# 140711_AriloTX_REV2_1_0.net
KiCad netlist of a schematic drawn in EAGLE
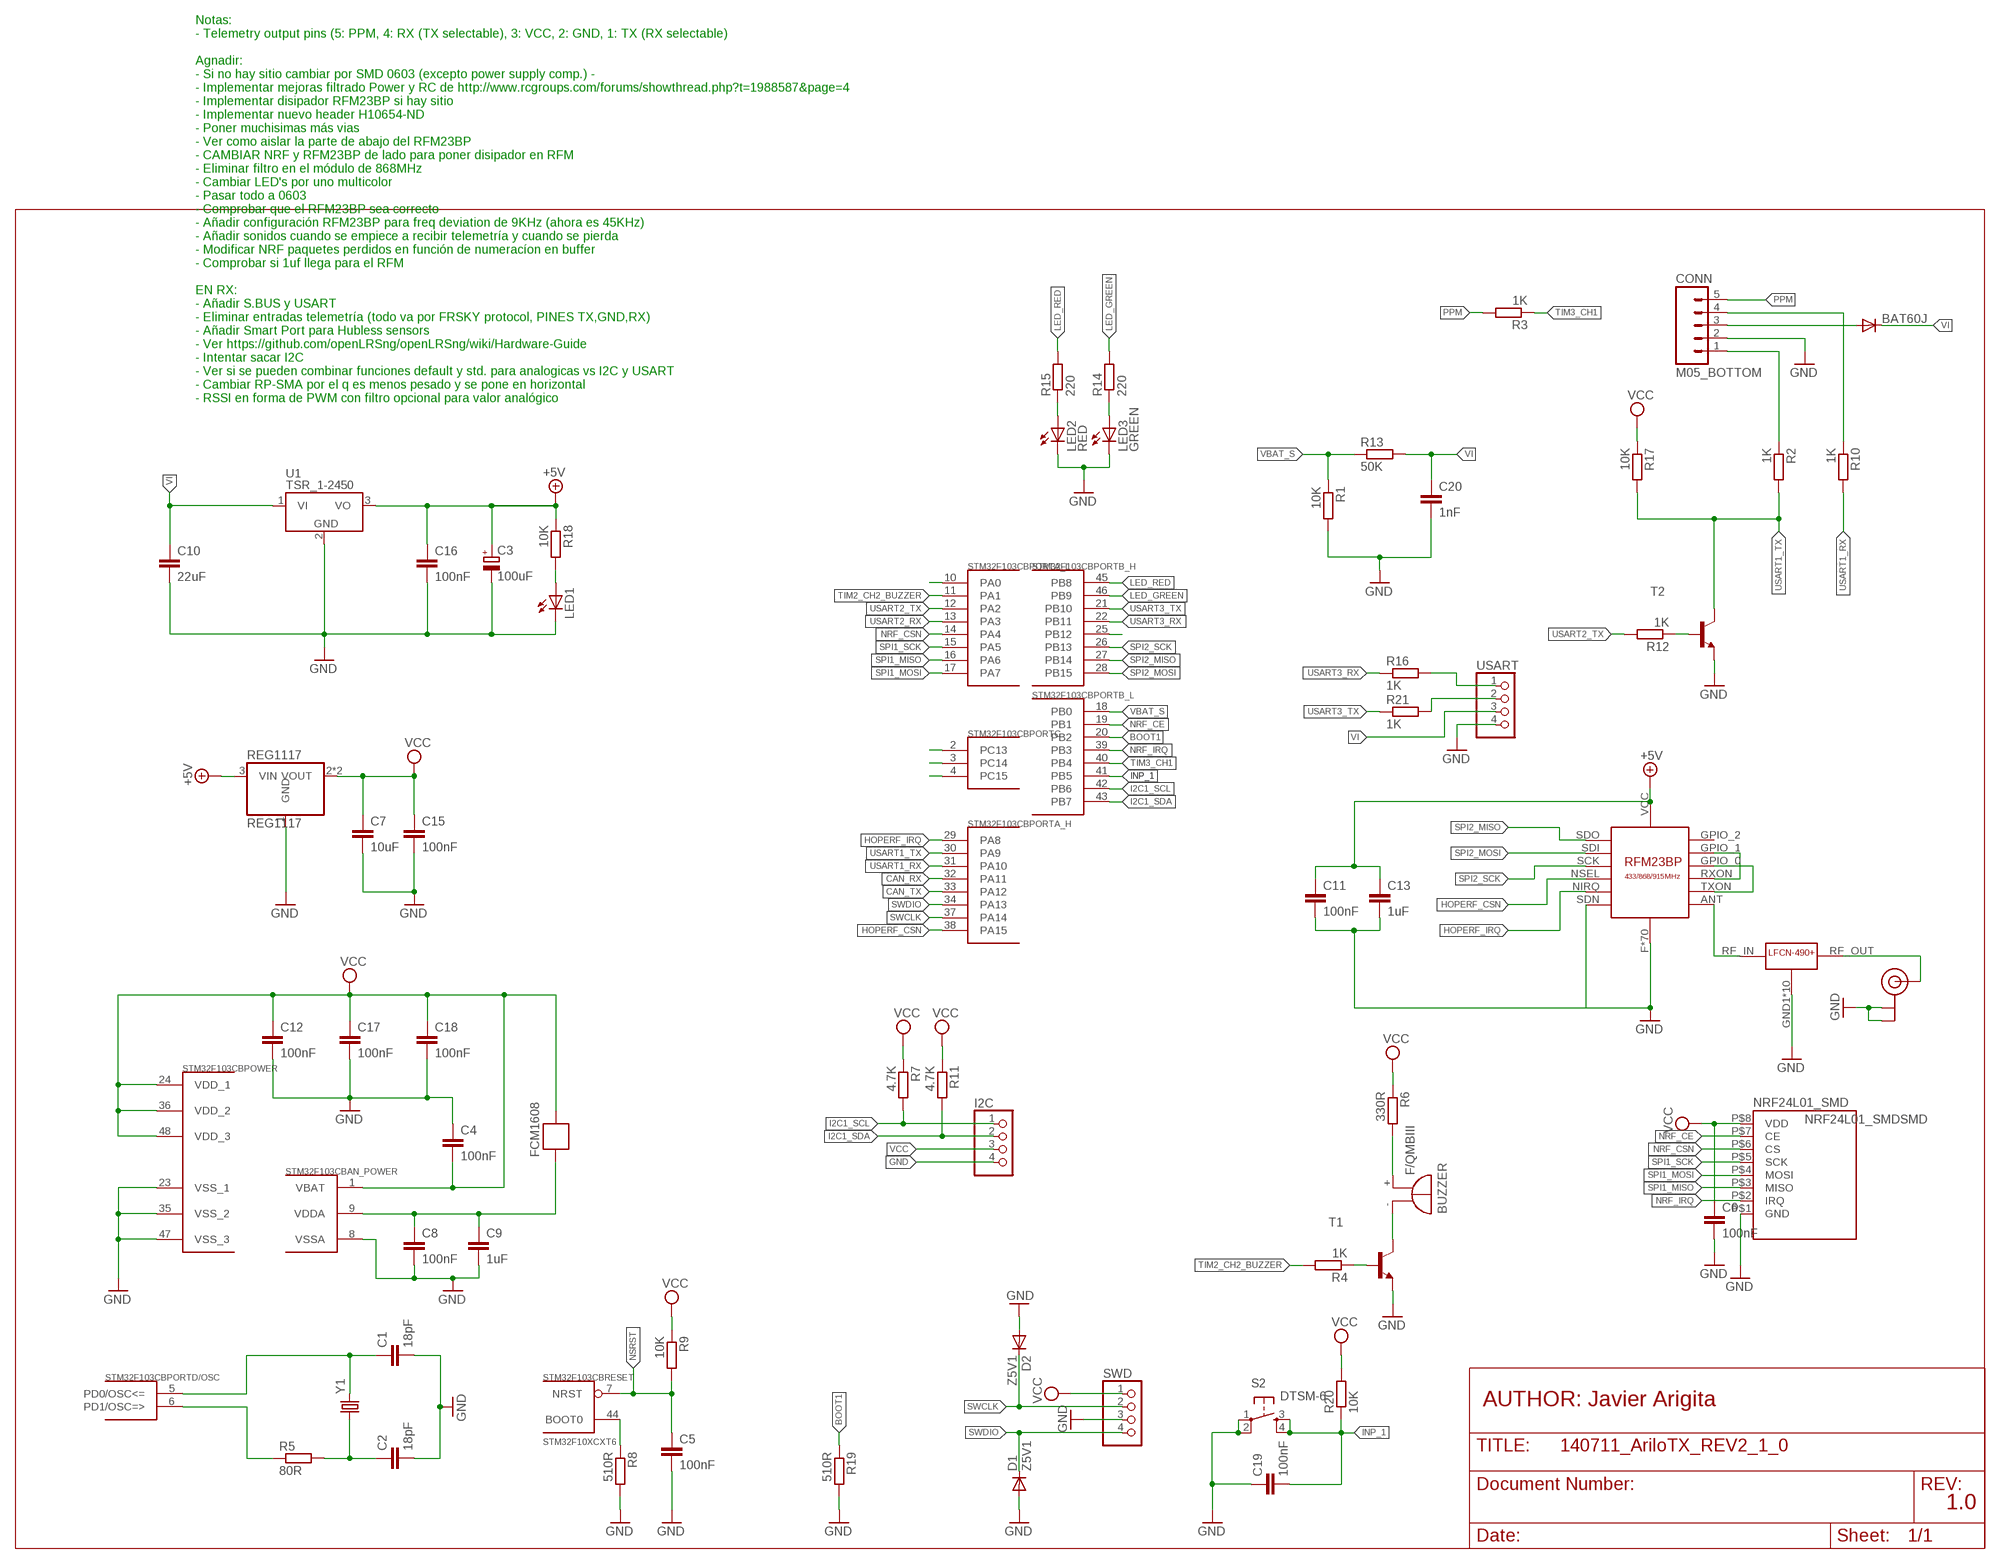
[diagram p0: schematic, sheet 1]

(export (version "E")
  (design (tool "Eeschema 10.0.6"))
  (components
    (comp (ref "BAT60J")
      (value "DIODE-SOD323-R")
      (footprint "eagle-import:SOD323-R")
      (libsource (lib "eagle-import") (part "DIODE-SOD323-R"))
    )
    (comp (ref "BUZZER")
      (value "F/QMBIII")
      (footprint "eagle-import:F_QMBIII")
      (libsource (lib "eagle-import") (part "F/QMBIII"))
    )
    (comp (ref "C1")
      (value "18pF")
      (footprint "eagle-import:C0603")
      (libsource (lib "eagle-import") (part "C-EUC0603"))
    )
    (comp (ref "C2")
      (value "18pF")
      (footprint "eagle-import:C0603")
      (libsource (lib "eagle-import") (part "C-EUC0603"))
    )
    (comp (ref "C3")
      (value "100uF")
      (footprint "eagle-import:SMC_B")
      (libsource (lib "eagle-import") (part "CPOL-EUSMCB"))
    )
    (comp (ref "C4")
      (value "100nF")
      (footprint "eagle-import:C0603")
      (libsource (lib "eagle-import") (part "C-EUC0603"))
    )
    (comp (ref "C5")
      (value "100nF")
      (footprint "eagle-import:C0603")
      (libsource (lib "eagle-import") (part "C-EUC0603"))
    )
    (comp (ref "C6")
      (value "100nF")
      (footprint "eagle-import:C0603")
      (libsource (lib "eagle-import") (part "C-EUC0603"))
    )
    (comp (ref "C7")
      (value "10uF")
      (footprint "eagle-import:C0805")
      (libsource (lib "eagle-import") (part "C-EUC0805"))
    )
    (comp (ref "C8")
      (value "100nF")
      (footprint "eagle-import:C0603")
      (libsource (lib "eagle-import") (part "C-EUC0603"))
    )
    (comp (ref "C9")
      (value "1uF")
      (footprint "eagle-import:C0603")
      (libsource (lib "eagle-import") (part "C-EUC0603"))
    )
    (comp (ref "C10")
      (value "22uF")
      (footprint "eagle-import:C3216")
      (libsource (lib "eagle-import") (part "resistor_C-EUC3216"))
    )
    (comp (ref "C11")
      (value "100nF")
      (footprint "eagle-import:C0603")
      (libsource (lib "eagle-import") (part "C-EUC0603"))
    )
    (comp (ref "C12")
      (value "100nF")
      (footprint "eagle-import:C0603")
      (libsource (lib "eagle-import") (part "C-EUC0603"))
    )
    (comp (ref "C13")
      (value "1uF")
      (footprint "eagle-import:C0603")
      (libsource (lib "eagle-import") (part "C-EUC0603"))
    )
    (comp (ref "C15")
      (value "100nF")
      (footprint "eagle-import:C0603")
      (libsource (lib "eagle-import") (part "C-EUC0603"))
    )
    (comp (ref "C16")
      (value "100nF")
      (footprint "eagle-import:C0603")
      (libsource (lib "eagle-import") (part "C-EUC0603"))
    )
    (comp (ref "C17")
      (value "100nF")
      (footprint "eagle-import:C0603")
      (libsource (lib "eagle-import") (part "C-EUC0603"))
    )
    (comp (ref "C18")
      (value "100nF")
      (footprint "eagle-import:C0603")
      (libsource (lib "eagle-import") (part "C-EUC0603"))
    )
    (comp (ref "C19")
      (value "100nF")
      (footprint "eagle-import:C0603")
      (libsource (lib "eagle-import") (part "C-EUC0603"))
    )
    (comp (ref "C20")
      (value "1nF")
      (footprint "eagle-import:C0603")
      (libsource (lib "eagle-import") (part "C-EUC0603"))
    )
    (comp (ref "CONN")
      (value "M05_BOTTOM")
      (footprint "eagle-import:M05_BOTTOM")
      (libsource (lib "eagle-import") (part "M05_BOTTOM"))
    )
    (comp (ref "D1")
      (value "Z5V1")
      (footprint "eagle-import:SOD323-R")
      (libsource (lib "eagle-import") (part "DIODE-SOD323-R"))
    )
    (comp (ref "D2")
      (value "Z5V1")
      (footprint "eagle-import:SOD323-R")
      (libsource (lib "eagle-import") (part "DIODE-SOD323-R"))
    )
    (comp (ref "FCM1608")
      (value "FERRITE-BEAD")
      (footprint "eagle-import:R0603")
      (libsource (lib "eagle-import") (part "FERRITE-BEAD"))
    )
    (comp (ref "I2C")
      (value "PINHD-1X4")
      (footprint "eagle-import:1X04")
      (libsource (lib "eagle-import") (part "PINHD-1X4"))
    )
    (comp (ref "LED1")
      (value "LEDCHIP-LED0603")
      (footprint "eagle-import:CHIP-LED0603")
      (libsource (lib "eagle-import") (part "LEDCHIP-LED0603"))
    )
    (comp (ref "LED2")
      (value "RED")
      (footprint "eagle-import:CHIP-LED0603")
      (libsource (lib "eagle-import") (part "LEDCHIP-LED0603"))
    )
    (comp (ref "LED3")
      (value "GREEN")
      (footprint "eagle-import:CHIP-LED0603")
      (libsource (lib "eagle-import") (part "LEDCHIP-LED0603"))
    )
    (comp (ref "NRF24L01_SMD")
      (value "NRF24L01_SMDSMD")
      (footprint "eagle-import:NRF24L01_SMD")
      (libsource (lib "eagle-import") (part "NRF24L01_SMDSMD"))
    )
    (comp (ref "R1")
      (value "10K")
      (footprint "eagle-import:R0603")
      (libsource (lib "eagle-import") (part "R-EU_R0603"))
    )
    (comp (ref "R2")
      (value "1K")
      (footprint "eagle-import:R0603")
      (libsource (lib "eagle-import") (part "R-EU_R0603"))
    )
    (comp (ref "R3")
      (value "1K")
      (footprint "eagle-import:R0603")
      (libsource (lib "eagle-import") (part "R-EU_R0603"))
    )
    (comp (ref "R4")
      (value "1K")
      (footprint "eagle-import:R0603")
      (libsource (lib "eagle-import") (part "R-EU_R0603"))
    )
    (comp (ref "R5")
      (value "80R")
      (footprint "eagle-import:R0603")
      (libsource (lib "eagle-import") (part "R-EU_R0603"))
    )
    (comp (ref "R6")
      (value "330R")
      (footprint "eagle-import:R0603")
      (libsource (lib "eagle-import") (part "R-EU_R0603"))
    )
    (comp (ref "R7")
      (value "4.7K")
      (footprint "eagle-import:R0603")
      (libsource (lib "eagle-import") (part "R-EU_R0603"))
    )
    (comp (ref "R8")
      (value "510R")
      (footprint "eagle-import:R0603")
      (libsource (lib "eagle-import") (part "R-EU_R0603"))
    )
    (comp (ref "R9")
      (value "10K")
      (footprint "eagle-import:R0603")
      (libsource (lib "eagle-import") (part "R-EU_R0603"))
    )
    (comp (ref "R10")
      (value "1K")
      (footprint "eagle-import:R0603")
      (libsource (lib "eagle-import") (part "R-EU_R0603"))
    )
    (comp (ref "R11")
      (value "4.7K")
      (footprint "eagle-import:R0603")
      (libsource (lib "eagle-import") (part "R-EU_R0603"))
    )
    (comp (ref "R12")
      (value "1K")
      (footprint "eagle-import:R0603")
      (libsource (lib "eagle-import") (part "R-EU_R0603"))
    )
    (comp (ref "R13")
      (value "50K")
      (footprint "eagle-import:R0603")
      (libsource (lib "eagle-import") (part "R-EU_R0603"))
    )
    (comp (ref "R14")
      (value "220")
      (footprint "eagle-import:R0603")
      (libsource (lib "eagle-import") (part "R-EU_R0603"))
    )
    (comp (ref "R15")
      (value "220")
      (footprint "eagle-import:R0603")
      (libsource (lib "eagle-import") (part "R-EU_R0603"))
    )
    (comp (ref "R16")
      (value "1K")
      (footprint "eagle-import:R0603")
      (libsource (lib "eagle-import") (part "R-EU_R0603"))
    )
    (comp (ref "R17")
      (value "10K")
      (footprint "eagle-import:R0603")
      (libsource (lib "eagle-import") (part "R-EU_R0603"))
    )
    (comp (ref "R18")
      (value "10K")
      (footprint "eagle-import:R0603")
      (libsource (lib "eagle-import") (part "R-EU_R0603"))
    )
    (comp (ref "R19")
      (value "510R")
      (footprint "eagle-import:R0603")
      (libsource (lib "eagle-import") (part "R-EU_R0603"))
    )
    (comp (ref "R20")
      (value "10K")
      (footprint "eagle-import:R0603")
      (libsource (lib "eagle-import") (part "R-EU_R0603"))
    )
    (comp (ref "R21")
      (value "1K")
      (footprint "eagle-import:R0603")
      (libsource (lib "eagle-import") (part "R-EU_R0603"))
    )
    (comp (ref "REG1117")
      (value "REG1117")
      (footprint "eagle-import:SOT223")
      (libsource (lib "eagle-import") (part "REG1117"))
    )
    (comp (ref "S2")
      (value "DTSM-6")
      (footprint "eagle-import:DTSM-6")
      (libsource (lib "eagle-import") (part "DTSM-6"))
    )
    (comp (ref "STM32F103CB")
      (value "STM32F10XCXT6")
      (footprint "eagle-import:TQFP48")
      (libsource (lib "eagle-import") (part "STM32F10XCXT6"))
    )
    (comp (ref "SWD")
      (value "PINHD-1X4")
      (footprint "eagle-import:1X04")
      (libsource (lib "eagle-import") (part "PINHD-1X4"))
    )
    (comp (ref "T1")
      (value "BC848-NPN-SOT23-BEC")
      (footprint "eagle-import:SOT23-BEC")
      (libsource (lib "eagle-import") (part "-NPN-SOT23-BECBC848"))
    )
    (comp (ref "T2")
      (value "BC848-NPN-SOT23-BEC")
      (footprint "eagle-import:SOT23-BEC")
      (libsource (lib "eagle-import") (part "-NPN-SOT23-BECBC848"))
    )
    (comp (ref "U$1")
      (value "RFM23BP")
      (footprint "eagle-import:RFM23BP")
      (libsource (lib "eagle-import") (part "RFM23BP"))
    )
    (comp (ref "U$2")
      (value "LFCN490+")
      (footprint "eagle-import:LFCN490+")
      (libsource (lib "eagle-import") (part "LFCN490+"))
    )
    (comp (ref "U$3")
      (value "U.FL")
      (footprint "eagle-import:U.FL")
      (libsource (lib "eagle-import") (part "U.FL"))
    )
    (comp (ref "U1")
      (value "TSR_1-2450")
      (footprint "eagle-import:TSR-1")
      (libsource (lib "eagle-import") (part "TSR_1-2450"))
    )
    (comp (ref "USART")
      (value "PINHD-1X4")
      (footprint "eagle-import:1X04")
      (libsource (lib "eagle-import") (part "PINHD-1X4"))
    )
    (comp (ref "Y1")
      (value "CRYSTAL5X3")
      (footprint "eagle-import:CRYSTAL-SMD-5X3")
      (libsource (lib "eagle-import") (part "CRYSTAL5X3"))
    )
  )
  (nets
    (net (code "1") (name "+5V") (class "Default")
      (node (ref "C11") (pin "1") (pinfunction "1_1") (pintype "passive"))
      (node (ref "C13") (pin "1") (pinfunction "1_1") (pintype "passive"))
      (node (ref "C16") (pin "1") (pinfunction "1_1") (pintype "passive"))
      (node (ref "C3") (pin "+") (pinfunction "+_+") (pintype "passive"))
      (node (ref "R18") (pin "1") (pinfunction "1_1") (pintype "passive"))
      (node (ref "REG1117") (pin "3") (pinfunction "VIN_3") (pintype "input"))
      (node (ref "U$1") (pin "VCC") (pinfunction "VCC_VCC") (pintype "power_in"))
      (node (ref "U1") (pin "3") (pinfunction "VO_3") (pintype "power_in"))
    )
    (net (code "2") (name "BOOT1") (class "Default")
      (node (ref "R19") (pin "1") (pinfunction "1_1") (pintype "passive"))
      (node (ref "STM32F103CB") (pin "20") (pinfunction "PB2_20") (pintype "bidirectional"))
    )
    (net (code "3") (name "CAN_RX") (class "Default")
      (node (ref "STM32F103CB") (pin "32") (pinfunction "PA11_32") (pintype "bidirectional"))
    )
    (net (code "4") (name "CAN_TX") (class "Default")
      (node (ref "STM32F103CB") (pin "33") (pinfunction "PA12_33") (pintype "bidirectional"))
    )
    (net (code "5") (name "GND") (class "Default")
      (node (ref "C1") (pin "2") (pinfunction "2_2") (pintype "passive"))
      (node (ref "C10") (pin "2") (pinfunction "2_2") (pintype "passive"))
      (node (ref "C11") (pin "2") (pinfunction "2_2") (pintype "passive"))
      (node (ref "C12") (pin "2") (pinfunction "2_2") (pintype "passive"))
      (node (ref "C13") (pin "2") (pinfunction "2_2") (pintype "passive"))
      (node (ref "C15") (pin "2") (pinfunction "2_2") (pintype "passive"))
      (node (ref "C16") (pin "2") (pinfunction "2_2") (pintype "passive"))
      (node (ref "C17") (pin "2") (pinfunction "2_2") (pintype "passive"))
      (node (ref "C18") (pin "2") (pinfunction "2_2") (pintype "passive"))
      (node (ref "C19") (pin "1") (pinfunction "1_1") (pintype "passive"))
      (node (ref "C2") (pin "2") (pinfunction "2_2") (pintype "passive"))
      (node (ref "C20") (pin "2") (pinfunction "2_2") (pintype "passive"))
      (node (ref "C3") (pin "-") (pinfunction "-_-") (pintype "passive"))
      (node (ref "C4") (pin "1") (pinfunction "1_1") (pintype "passive"))
      (node (ref "C5") (pin "2") (pinfunction "2_2") (pintype "passive"))
      (node (ref "C6") (pin "2") (pinfunction "2_2") (pintype "passive"))
      (node (ref "C7") (pin "2") (pinfunction "2_2") (pintype "passive"))
      (node (ref "C8") (pin "2") (pinfunction "2_2") (pintype "passive"))
      (node (ref "C9") (pin "2") (pinfunction "2_2") (pintype "passive"))
      (node (ref "CONN") (pin "2") (pinfunction "2_2") (pintype "passive"))
      (node (ref "D1") (pin "A") (pinfunction "A_A") (pintype "passive"))
      (node (ref "D2") (pin "A") (pinfunction "A_A") (pintype "passive"))
      (node (ref "I2C") (pin "4") (pinfunction "4_4") (pintype "passive"))
      (node (ref "LED1") (pin "C") (pinfunction "C_C") (pintype "passive"))
      (node (ref "LED2") (pin "C") (pinfunction "C_C") (pintype "passive"))
      (node (ref "LED3") (pin "C") (pinfunction "C_C") (pintype "passive"))
      (node (ref "NRF24L01_SMD") (pin "P$1") (pinfunction "GND_P$1") (pintype "power_in"))
      (node (ref "R1") (pin "2") (pinfunction "2_2") (pintype "passive"))
      (node (ref "R19") (pin "2") (pinfunction "2_2") (pintype "passive"))
      (node (ref "R8") (pin "2") (pinfunction "2_2") (pintype "passive"))
      (node (ref "REG1117") (pin "1") (pinfunction "GND_1") (pintype "power_in"))
      (node (ref "S2") (pin "1") (pinfunction "1_1") (pintype "passive"))
      (node (ref "S2") (pin "2") (pinfunction "2_2") (pintype "passive"))
      (node (ref "STM32F103CB") (pin "23") (pinfunction "VSS_1_23") (pintype "power_in"))
      (node (ref "STM32F103CB") (pin "35") (pinfunction "VSS_2_35") (pintype "power_in"))
      (node (ref "STM32F103CB") (pin "47") (pinfunction "VSS_3_47") (pintype "power_in"))
      (node (ref "STM32F103CB") (pin "8") (pinfunction "VSSA_8") (pintype "power_in"))
      (node (ref "SWD") (pin "3") (pinfunction "3_3") (pintype "passive"))
      (node (ref "T1") (pin "E") (pinfunction "E_E") (pintype "passive"))
      (node (ref "T2") (pin "E") (pinfunction "E_E") (pintype "passive"))
      (node (ref "U$1") (pin "F") (pinfunction "GND_F") (pintype "power_in"))
      (node (ref "U$1") (pin "F1") (pinfunction "GND_F1") (pintype "power_in"))
      (node (ref "U$1") (pin "F10") (pinfunction "GND_F10") (pintype "power_in"))
      (node (ref "U$1") (pin "F11") (pinfunction "GND_F11") (pintype "power_in"))
      (node (ref "U$1") (pin "F12") (pinfunction "GND_F12") (pintype "power_in"))
      (node (ref "U$1") (pin "F13") (pinfunction "GND_F13") (pintype "power_in"))
      (node (ref "U$1") (pin "F14") (pinfunction "GND_F14") (pintype "power_in"))
      (node (ref "U$1") (pin "F15") (pinfunction "GND_F15") (pintype "power_in"))
      (node (ref "U$1") (pin "F16") (pinfunction "GND_F16") (pintype "power_in"))
      (node (ref "U$1") (pin "F17") (pinfunction "GND_F17") (pintype "power_in"))
      (node (ref "U$1") (pin "F18") (pinfunction "GND_F18") (pintype "power_in"))
      (node (ref "U$1") (pin "F19") (pinfunction "GND_F19") (pintype "power_in"))
      (node (ref "U$1") (pin "F2") (pinfunction "GND_F2") (pintype "power_in"))
      (node (ref "U$1") (pin "F20") (pinfunction "GND_F20") (pintype "power_in"))
      (node (ref "U$1") (pin "F21") (pinfunction "GND_F21") (pintype "power_in"))
      (node (ref "U$1") (pin "F22") (pinfunction "GND_F22") (pintype "power_in"))
      (node (ref "U$1") (pin "F23") (pinfunction "GND_F23") (pintype "power_in"))
      (node (ref "U$1") (pin "F24") (pinfunction "GND_F24") (pintype "power_in"))
      (node (ref "U$1") (pin "F25") (pinfunction "GND_F25") (pintype "power_in"))
      (node (ref "U$1") (pin "F26") (pinfunction "GND_F26") (pintype "power_in"))
      (node (ref "U$1") (pin "F27") (pinfunction "GND_F27") (pintype "power_in"))
      (node (ref "U$1") (pin "F28") (pinfunction "GND_F28") (pintype "power_in"))
      (node (ref "U$1") (pin "F29") (pinfunction "GND_F29") (pintype "power_in"))
      (node (ref "U$1") (pin "F3") (pinfunction "GND_F3") (pintype "power_in"))
      (node (ref "U$1") (pin "F30") (pinfunction "GND_F30") (pintype "power_in"))
      (node (ref "U$1") (pin "F31") (pinfunction "GND_F31") (pintype "power_in"))
      (node (ref "U$1") (pin "F32") (pinfunction "GND_F32") (pintype "power_in"))
      (node (ref "U$1") (pin "F33") (pinfunction "GND_F33") (pintype "power_in"))
      (node (ref "U$1") (pin "F34") (pinfunction "GND_F34") (pintype "power_in"))
      (node (ref "U$1") (pin "F35") (pinfunction "GND_F35") (pintype "power_in"))
      (node (ref "U$1") (pin "F36") (pinfunction "GND_F36") (pintype "power_in"))
      (node (ref "U$1") (pin "F37") (pinfunction "GND_F37") (pintype "power_in"))
      (node (ref "U$1") (pin "F38") (pinfunction "GND_F38") (pintype "power_in"))
      (node (ref "U$1") (pin "F39") (pinfunction "GND_F39") (pintype "power_in"))
      (node (ref "U$1") (pin "F4") (pinfunction "GND_F4") (pintype "power_in"))
      (node (ref "U$1") (pin "F40") (pinfunction "GND_F40") (pintype "power_in"))
      (node (ref "U$1") (pin "F41") (pinfunction "GND_F41") (pintype "power_in"))
      (node (ref "U$1") (pin "F42") (pinfunction "GND_F42") (pintype "power_in"))
      (node (ref "U$1") (pin "F43") (pinfunction "GND_F43") (pintype "power_in"))
      (node (ref "U$1") (pin "F44") (pinfunction "GND_F44") (pintype "power_in"))
      (node (ref "U$1") (pin "F45") (pinfunction "GND_F45") (pintype "power_in"))
      (node (ref "U$1") (pin "F46") (pinfunction "GND_F46") (pintype "power_in"))
      (node (ref "U$1") (pin "F47") (pinfunction "GND_F47") (pintype "power_in"))
      (node (ref "U$1") (pin "F48") (pinfunction "GND_F48") (pintype "power_in"))
      (node (ref "U$1") (pin "F49") (pinfunction "GND_F49") (pintype "power_in"))
      (node (ref "U$1") (pin "F5") (pinfunction "GND_F5") (pintype "power_in"))
      (node (ref "U$1") (pin "F50") (pinfunction "GND_F50") (pintype "power_in"))
      (node (ref "U$1") (pin "F51") (pinfunction "GND_F51") (pintype "power_in"))
      (node (ref "U$1") (pin "F52") (pinfunction "GND_F52") (pintype "power_in"))
      (node (ref "U$1") (pin "F53") (pinfunction "GND_F53") (pintype "power_in"))
      (node (ref "U$1") (pin "F54") (pinfunction "GND_F54") (pintype "power_in"))
      (node (ref "U$1") (pin "F55") (pinfunction "GND_F55") (pintype "power_in"))
      (node (ref "U$1") (pin "F56") (pinfunction "GND_F56") (pintype "power_in"))
      (node (ref "U$1") (pin "F57") (pinfunction "GND_F57") (pintype "power_in"))
      (node (ref "U$1") (pin "F58") (pinfunction "GND_F58") (pintype "power_in"))
      (node (ref "U$1") (pin "F59") (pinfunction "GND_F59") (pintype "power_in"))
      (node (ref "U$1") (pin "F6") (pinfunction "GND_F6") (pintype "power_in"))
      (node (ref "U$1") (pin "F60") (pinfunction "GND_F60") (pintype "power_in"))
      (node (ref "U$1") (pin "F61") (pinfunction "GND_F61") (pintype "power_in"))
      (node (ref "U$1") (pin "F62") (pinfunction "GND_F62") (pintype "power_in"))
      (node (ref "U$1") (pin "F63") (pinfunction "GND_F63") (pintype "power_in"))
      (node (ref "U$1") (pin "F64") (pinfunction "GND_F64") (pintype "power_in"))
      (node (ref "U$1") (pin "F65") (pinfunction "GND_F65") (pintype "power_in"))
      (node (ref "U$1") (pin "F7") (pinfunction "GND_F7") (pintype "power_in"))
      (node (ref "U$1") (pin "F8") (pinfunction "GND_F8") (pintype "power_in"))
      (node (ref "U$1") (pin "F9") (pinfunction "GND_F9") (pintype "power_in"))
      (node (ref "U$1") (pin "GND1") (pinfunction "GND_GND1") (pintype "power_in"))
      (node (ref "U$1") (pin "GND2") (pinfunction "GND_GND2") (pintype "power_in"))
      (node (ref "U$1") (pin "GND3") (pinfunction "GND_GND3") (pintype "power_in"))
      (node (ref "U$1") (pin "GND_HEAT") (pinfunction "GND_GND_HEAT") (pintype "power_in"))
      (node (ref "U$1") (pin "SDN") (pinfunction "SDN_SDN") (pintype "bidirectional"))
      (node (ref "U$2") (pin "GND1") (pinfunction "GND_GND1") (pintype "bidirectional"))
      (node (ref "U$2") (pin "GND10") (pinfunction "GND_GND10") (pintype "bidirectional"))
      (node (ref "U$2") (pin "GND2") (pinfunction "GND_GND2") (pintype "bidirectional"))
      (node (ref "U$2") (pin "GND3") (pinfunction "GND_GND3") (pintype "bidirectional"))
      (node (ref "U$2") (pin "GND4") (pinfunction "GND_GND4") (pintype "bidirectional"))
      (node (ref "U$2") (pin "GND5") (pinfunction "GND_GND5") (pintype "bidirectional"))
      (node (ref "U$2") (pin "GND6") (pinfunction "GND_GND6") (pintype "bidirectional"))
      (node (ref "U$2") (pin "GND7") (pinfunction "GND_GND7") (pintype "bidirectional"))
      (node (ref "U$2") (pin "GND8") (pinfunction "GND_GND8") (pintype "bidirectional"))
      (node (ref "U$2") (pin "GND9") (pinfunction "GND_GND9") (pintype "bidirectional"))
      (node (ref "U$3") (pin "P$1") (pinfunction "GND_P$1") (pintype "bidirectional"))
      (node (ref "U$3") (pin "P$2") (pinfunction "GND_P$2") (pintype "bidirectional"))
      (node (ref "U1") (pin "2") (pinfunction "GND_2") (pintype "power_in"))
      (node (ref "USART") (pin "4") (pinfunction "4_4") (pintype "passive"))
    )
    (net (code "6") (name "HOPERF_CSN") (class "Default")
      (node (ref "STM32F103CB") (pin "38") (pinfunction "PA15_38") (pintype "bidirectional"))
      (node (ref "U$1") (pin "NSEL") (pinfunction "NSEL_NSEL") (pintype "bidirectional"))
    )
    (net (code "7") (name "HOPERF_IRQ") (class "Default")
      (node (ref "STM32F103CB") (pin "29") (pinfunction "PA8_29") (pintype "bidirectional"))
      (node (ref "U$1") (pin "NIRQ") (pinfunction "NIRQ_NIRQ") (pintype "bidirectional"))
    )
    (net (code "8") (name "I2C1_SCL") (class "Default")
      (node (ref "I2C") (pin "1") (pinfunction "1_1") (pintype "passive"))
      (node (ref "R7") (pin "2") (pinfunction "2_2") (pintype "passive"))
      (node (ref "STM32F103CB") (pin "42") (pinfunction "PB6_42") (pintype "bidirectional"))
    )
    (net (code "9") (name "I2C1_SDA") (class "Default")
      (node (ref "I2C") (pin "2") (pinfunction "2_2") (pintype "passive"))
      (node (ref "R11") (pin "2") (pinfunction "2_2") (pintype "passive"))
      (node (ref "STM32F103CB") (pin "43") (pinfunction "PB7_43") (pintype "bidirectional"))
    )
    (net (code "10") (name "INP_1") (class "Default")
      (node (ref "C19") (pin "2") (pinfunction "2_2") (pintype "passive"))
      (node (ref "R20") (pin "1") (pinfunction "1_1") (pintype "passive"))
      (node (ref "S2") (pin "3") (pinfunction "3_3") (pintype "passive"))
      (node (ref "S2") (pin "4") (pinfunction "4_4") (pintype "passive"))
      (node (ref "STM32F103CB") (pin "41") (pinfunction "PB5_41") (pintype "bidirectional"))
    )
    (net (code "11") (name "LED_GREEN") (class "Default")
      (node (ref "R14") (pin "2") (pinfunction "2_2") (pintype "passive"))
      (node (ref "STM32F103CB") (pin "46") (pinfunction "PB9_46") (pintype "bidirectional"))
    )
    (net (code "12") (name "LED_RED") (class "Default")
      (node (ref "R15") (pin "2") (pinfunction "2_2") (pintype "passive"))
      (node (ref "STM32F103CB") (pin "45") (pinfunction "PB8_45") (pintype "bidirectional"))
    )
    (net (code "13") (name "NRF_CE") (class "Default")
      (node (ref "NRF24L01_SMD") (pin "P$7") (pinfunction "CE_P$7") (pintype "input"))
      (node (ref "STM32F103CB") (pin "19") (pinfunction "PB1_19") (pintype "bidirectional"))
    )
    (net (code "14") (name "NRF_CSN") (class "Default")
      (node (ref "NRF24L01_SMD") (pin "P$6") (pinfunction "CS_P$6") (pintype "input"))
      (node (ref "STM32F103CB") (pin "14") (pinfunction "PA4_14") (pintype "bidirectional"))
    )
    (net (code "15") (name "NRF_IRQ") (class "Default")
      (node (ref "NRF24L01_SMD") (pin "P$2") (pinfunction "IRQ_P$2") (pintype "output"))
      (node (ref "STM32F103CB") (pin "39") (pinfunction "PB3_39") (pintype "bidirectional"))
    )
    (net (code "16") (name "NSRST") (class "Default")
      (node (ref "C5") (pin "1") (pinfunction "1_1") (pintype "passive"))
      (node (ref "R9") (pin "2") (pinfunction "2_2") (pintype "passive"))
      (node (ref "STM32F103CB") (pin "7") (pinfunction "NRST_7") (pintype "input"))
    )
    (net (code "17") (name "Net-(BAT60J-PadA)") (class "Default")
      (node (ref "BAT60J") (pin "A") (pinfunction "A_A") (pintype "passive"))
      (node (ref "CONN") (pin "3") (pinfunction "3_3") (pintype "passive"))
    )
    (net (code "18") (name "Net-(BUZZER-+)") (class "Default")
      (node (ref "BUZZER") (pin "-") (pinfunction "+_-") (pintype "passive"))
      (node (ref "T1") (pin "C") (pinfunction "C_C") (pintype "passive"))
    )
    (net (code "19") (name "Net-(BUZZER--)") (class "Default")
      (node (ref "BUZZER") (pin "+") (pinfunction "-_+") (pintype "passive"))
      (node (ref "R6") (pin "2") (pinfunction "2_2") (pintype "passive"))
    )
    (net (code "20") (name "Net-(C2-Pad1)") (class "Default")
      (node (ref "C2") (pin "1") (pinfunction "1_1") (pintype "passive"))
      (node (ref "R5") (pin "2") (pinfunction "2_2") (pintype "passive"))
      (node (ref "Y1") (pin "1") (pinfunction "1_1") (pintype "passive"))
    )
    (net (code "21") (name "Net-(CONN-Pad1)") (class "Default")
      (node (ref "CONN") (pin "1") (pinfunction "1_1") (pintype "passive"))
      (node (ref "R2") (pin "1") (pinfunction "1_1") (pintype "passive"))
    )
    (net (code "22") (name "Net-(CONN-Pad4)") (class "Default")
      (node (ref "CONN") (pin "4") (pinfunction "4_4") (pintype "passive"))
      (node (ref "R10") (pin "1") (pinfunction "1_1") (pintype "passive"))
    )
    (net (code "23") (name "Net-(FCM1608-P$2)") (class "Default")
      (node (ref "C8") (pin "1") (pinfunction "1_1") (pintype "passive"))
      (node (ref "C9") (pin "1") (pinfunction "1_1") (pintype "passive"))
      (node (ref "FCM1608") (pin "2") (pinfunction "P$2_2") (pintype "bidirectional"))
      (node (ref "STM32F103CB") (pin "9") (pinfunction "VDDA_9") (pintype "power_in"))
    )
    (net (code "24") (name "Net-(LED1-PadA)") (class "Default")
      (node (ref "LED1") (pin "A") (pinfunction "A_A") (pintype "passive"))
      (node (ref "R18") (pin "2") (pinfunction "2_2") (pintype "passive"))
    )
    (net (code "25") (name "Net-(LED2-PadA)") (class "Default")
      (node (ref "LED2") (pin "A") (pinfunction "A_A") (pintype "passive"))
      (node (ref "R15") (pin "1") (pinfunction "1_1") (pintype "passive"))
    )
    (net (code "26") (name "Net-(LED3-PadA)") (class "Default")
      (node (ref "LED3") (pin "A") (pinfunction "A_A") (pintype "passive"))
      (node (ref "R14") (pin "1") (pinfunction "1_1") (pintype "passive"))
    )
    (net (code "27") (name "Net-(R4-Pad1)") (class "Default")
      (node (ref "R4") (pin "1") (pinfunction "1_1") (pintype "passive"))
      (node (ref "T1") (pin "B") (pinfunction "B_B") (pintype "passive"))
    )
    (net (code "28") (name "Net-(R12-Pad1)") (class "Default")
      (node (ref "R12") (pin "1") (pinfunction "1_1") (pintype "passive"))
      (node (ref "T2") (pin "B") (pinfunction "B_B") (pintype "passive"))
    )
    (net (code "29") (name "Net-(R16-Pad2)") (class "Default")
      (node (ref "R16") (pin "2") (pinfunction "2_2") (pintype "passive"))
      (node (ref "USART") (pin "1") (pinfunction "1_1") (pintype "passive"))
    )
    (net (code "30") (name "Net-(R21-Pad2)") (class "Default")
      (node (ref "R21") (pin "2") (pinfunction "2_2") (pintype "passive"))
      (node (ref "USART") (pin "2") (pinfunction "2_2") (pintype "passive"))
    )
    (net (code "31") (name "Net-(STM32F103CBG-PD0{slash}OSC<=)") (class "Default")
      (node (ref "C1") (pin "1") (pinfunction "1_1") (pintype "passive"))
      (node (ref "STM32F103CB") (pin "5") (pinfunction "PD0/OSC<=_5") (pintype "bidirectional"))
      (node (ref "Y1") (pin "3") (pinfunction "2_3") (pintype "passive"))
    )
    (net (code "32") (name "Net-(STM32F103CBG-PD1{slash}OSC=>)") (class "Default")
      (node (ref "R5") (pin "1") (pinfunction "1_1") (pintype "passive"))
      (node (ref "STM32F103CB") (pin "6") (pinfunction "PD1/OSC=>_6") (pintype "bidirectional"))
    )
    (net (code "33") (name "Net-(STM32F103CBI-BOOT0)") (class "Default")
      (node (ref "R8") (pin "1") (pinfunction "1_1") (pintype "passive"))
      (node (ref "STM32F103CB") (pin "44") (pinfunction "BOOT0_44") (pintype "input"))
    )
    (net (code "34") (name "Net-(U$1-PadGPIO_0)") (class "Default")
      (node (ref "U$1") (pin "GPIO_0") (pinfunction "GPIO_0_GPIO_0") (pintype "bidirectional"))
      (node (ref "U$1") (pin "TXON") (pinfunction "TXON_TXON") (pintype "bidirectional"))
    )
    (net (code "35") (name "Net-(U$1-PadGPIO_1)") (class "Default")
      (node (ref "U$1") (pin "GPIO_1") (pinfunction "GPIO_1_GPIO_1") (pintype "bidirectional"))
      (node (ref "U$1") (pin "RXON") (pinfunction "RXON_RXON") (pintype "bidirectional"))
    )
    (net (code "36") (name "Net-(U$2-RF_INP)") (class "Default")
      (node (ref "U$1") (pin "ANT") (pinfunction "ANT_ANT") (pintype "bidirectional"))
      (node (ref "U$2") (pin "RF_IN") (pinfunction "RF_INP_RF_IN") (pintype "bidirectional"))
    )
    (net (code "37") (name "Net-(U$2-RF_OUTP)") (class "Default")
      (node (ref "U$2") (pin "RF_OUT") (pinfunction "RF_OUTP_RF_OUT") (pintype "bidirectional"))
      (node (ref "U$3") (pin "P$3") (pinfunction "SIGNAL_P$3") (pintype "bidirectional"))
    )
    (net (code "38") (name "PPM") (class "Default")
      (node (ref "CONN") (pin "5") (pinfunction "5_5") (pintype "passive"))
      (node (ref "R3") (pin "2") (pinfunction "2_2") (pintype "passive"))
    )
    (net (code "39") (name "SPI1_MISO") (class "Default")
      (node (ref "NRF24L01_SMD") (pin "P$3") (pinfunction "MISO_P$3") (pintype "output"))
      (node (ref "STM32F103CB") (pin "16") (pinfunction "PA6_16") (pintype "bidirectional"))
    )
    (net (code "40") (name "SPI1_MOSI") (class "Default")
      (node (ref "NRF24L01_SMD") (pin "P$4") (pinfunction "MOSI_P$4") (pintype "input"))
      (node (ref "STM32F103CB") (pin "17") (pinfunction "PA7_17") (pintype "bidirectional"))
    )
    (net (code "41") (name "SPI1_SCK") (class "Default")
      (node (ref "NRF24L01_SMD") (pin "P$5") (pinfunction "SCK_P$5") (pintype "input"))
      (node (ref "STM32F103CB") (pin "15") (pinfunction "PA5_15") (pintype "bidirectional"))
    )
    (net (code "42") (name "SPI2_MISO") (class "Default")
      (node (ref "STM32F103CB") (pin "27") (pinfunction "PB14_27") (pintype "bidirectional"))
      (node (ref "U$1") (pin "SDO") (pinfunction "SDO_SDO") (pintype "bidirectional"))
    )
    (net (code "43") (name "SPI2_MOSI") (class "Default")
      (node (ref "STM32F103CB") (pin "28") (pinfunction "PB15_28") (pintype "bidirectional"))
      (node (ref "U$1") (pin "SDI") (pinfunction "SDI_SDI") (pintype "bidirectional"))
    )
    (net (code "44") (name "SPI2_SCK") (class "Default")
      (node (ref "STM32F103CB") (pin "26") (pinfunction "PB13_26") (pintype "bidirectional"))
      (node (ref "U$1") (pin "SCK") (pinfunction "SCK_SCK") (pintype "bidirectional"))
    )
    (net (code "45") (name "SWCLK") (class "Default")
      (node (ref "D2") (pin "C") (pinfunction "C_C") (pintype "passive"))
      (node (ref "STM32F103CB") (pin "37") (pinfunction "PA14_37") (pintype "bidirectional"))
      (node (ref "SWD") (pin "2") (pinfunction "2_2") (pintype "passive"))
    )
    (net (code "46") (name "SWDIO") (class "Default")
      (node (ref "D1") (pin "C") (pinfunction "C_C") (pintype "passive"))
      (node (ref "STM32F103CB") (pin "34") (pinfunction "PA13_34") (pintype "bidirectional"))
      (node (ref "SWD") (pin "4") (pinfunction "4_4") (pintype "passive"))
    )
    (net (code "47") (name "TIM2_CH2_BUZZER") (class "Default")
      (node (ref "R4") (pin "2") (pinfunction "2_2") (pintype "passive"))
      (node (ref "STM32F103CB") (pin "11") (pinfunction "PA1_11") (pintype "bidirectional"))
    )
    (net (code "48") (name "TIM3_CH1") (class "Default")
      (node (ref "R3") (pin "1") (pinfunction "1_1") (pintype "passive"))
      (node (ref "STM32F103CB") (pin "40") (pinfunction "PB4_40") (pintype "bidirectional"))
    )
    (net (code "49") (name "USART1_RX") (class "Default")
      (node (ref "R10") (pin "2") (pinfunction "2_2") (pintype "passive"))
      (node (ref "STM32F103CB") (pin "31") (pinfunction "PA10_31") (pintype "bidirectional"))
    )
    (net (code "50") (name "USART1_TX") (class "Default")
      (node (ref "R17") (pin "2") (pinfunction "2_2") (pintype "passive"))
      (node (ref "R2") (pin "2") (pinfunction "2_2") (pintype "passive"))
      (node (ref "STM32F103CB") (pin "30") (pinfunction "PA9_30") (pintype "bidirectional"))
      (node (ref "T2") (pin "C") (pinfunction "C_C") (pintype "passive"))
    )
    (net (code "51") (name "USART2_RX") (class "Default")
      (node (ref "STM32F103CB") (pin "13") (pinfunction "PA3_13") (pintype "bidirectional"))
    )
    (net (code "52") (name "USART2_TX") (class "Default")
      (node (ref "R12") (pin "2") (pinfunction "2_2") (pintype "passive"))
      (node (ref "STM32F103CB") (pin "12") (pinfunction "PA2_12") (pintype "bidirectional"))
    )
    (net (code "53") (name "USART3_RX") (class "Default")
      (node (ref "R16") (pin "1") (pinfunction "1_1") (pintype "passive"))
      (node (ref "STM32F103CB") (pin "22") (pinfunction "PB11_22") (pintype "bidirectional"))
    )
    (net (code "54") (name "USART3_TX") (class "Default")
      (node (ref "R21") (pin "1") (pinfunction "1_1") (pintype "passive"))
      (node (ref "STM32F103CB") (pin "21") (pinfunction "PB10_21") (pintype "bidirectional"))
    )
    (net (code "55") (name "VBAT_S") (class "Default")
      (node (ref "R1") (pin "1") (pinfunction "1_1") (pintype "passive"))
      (node (ref "R13") (pin "1") (pinfunction "1_1") (pintype "passive"))
      (node (ref "STM32F103CB") (pin "18") (pinfunction "PB0_18") (pintype "bidirectional"))
    )
    (net (code "56") (name "VCC") (class "Default")
      (node (ref "C12") (pin "1") (pinfunction "1_1") (pintype "passive"))
      (node (ref "C15") (pin "1") (pinfunction "1_1") (pintype "passive"))
      (node (ref "C17") (pin "1") (pinfunction "1_1") (pintype "passive"))
      (node (ref "C18") (pin "1") (pinfunction "1_1") (pintype "passive"))
      (node (ref "C4") (pin "2") (pinfunction "2_2") (pintype "passive"))
      (node (ref "C6") (pin "1") (pinfunction "1_1") (pintype "passive"))
      (node (ref "C7") (pin "1") (pinfunction "1_1") (pintype "passive"))
      (node (ref "FCM1608") (pin "1") (pinfunction "P$1_1") (pintype "bidirectional"))
      (node (ref "I2C") (pin "3") (pinfunction "3_3") (pintype "passive"))
      (node (ref "NRF24L01_SMD") (pin "P$8") (pinfunction "VDD_P$8") (pintype "bidirectional"))
      (node (ref "R11") (pin "1") (pinfunction "1_1") (pintype "passive"))
      (node (ref "R17") (pin "1") (pinfunction "1_1") (pintype "passive"))
      (node (ref "R20") (pin "2") (pinfunction "2_2") (pintype "passive"))
      (node (ref "R6") (pin "1") (pinfunction "1_1") (pintype "passive"))
      (node (ref "R7") (pin "1") (pinfunction "1_1") (pintype "passive"))
      (node (ref "R9") (pin "1") (pinfunction "1_1") (pintype "passive"))
      (node (ref "REG1117") (pin "2") (pinfunction "VOUT_2") (pintype "power_in"))
      (node (ref "REG1117") (pin "4") (pinfunction "VOUT_4") (pintype "power_in"))
      (node (ref "STM32F103CB") (pin "1") (pinfunction "VBAT_1") (pintype "power_in"))
      (node (ref "STM32F103CB") (pin "24") (pinfunction "VDD_1_24") (pintype "power_in"))
      (node (ref "STM32F103CB") (pin "36") (pinfunction "VDD_2_36") (pintype "power_in"))
      (node (ref "STM32F103CB") (pin "48") (pinfunction "VDD_3_48") (pintype "power_in"))
      (node (ref "SWD") (pin "1") (pinfunction "1_1") (pintype "passive"))
    )
    (net (code "57") (name "VI") (class "Default")
      (node (ref "BAT60J") (pin "C") (pinfunction "C_C") (pintype "passive"))
      (node (ref "C10") (pin "1") (pinfunction "1_1") (pintype "passive"))
      (node (ref "C20") (pin "1") (pinfunction "1_1") (pintype "passive"))
      (node (ref "R13") (pin "2") (pinfunction "2_2") (pintype "passive"))
      (node (ref "U1") (pin "1") (pinfunction "VI_1") (pintype "power_in"))
      (node (ref "USART") (pin "3") (pinfunction "3_3") (pintype "passive"))
    )
    (net (code "58") (name "unconnected-(STM32F103CBC-PA0-Pad10)") (class "Default")
      (node (ref "STM32F103CB") (pin "10") (pinfunction "PA0_10") (pintype "bidirectional"))
    )
    (net (code "59") (name "unconnected-(STM32F103CBD-PB12-Pad25)") (class "Default")
      (node (ref "STM32F103CB") (pin "25") (pinfunction "PB12_25") (pintype "bidirectional"))
    )
    (net (code "60") (name "unconnected-(STM32F103CBF-PC13-Pad2)") (class "Default")
      (node (ref "STM32F103CB") (pin "2") (pinfunction "PC13_2") (pintype "bidirectional"))
    )
    (net (code "61") (name "unconnected-(STM32F103CBF-PC14-Pad3)") (class "Default")
      (node (ref "STM32F103CB") (pin "3") (pinfunction "PC14_3") (pintype "bidirectional"))
    )
    (net (code "62") (name "unconnected-(STM32F103CBF-PC15-Pad4)") (class "Default")
      (node (ref "STM32F103CB") (pin "4") (pinfunction "PC15_4") (pintype "bidirectional"))
    )
    (net (code "63") (name "unconnected-(U$1-PadGPIO_2)") (class "Default")
      (node (ref "U$1") (pin "GPIO_2") (pinfunction "GPIO_2_GPIO_2") (pintype "bidirectional"))
    )
  )
)
